# Transfer_V1_Sch.net
KiCad netlist of a schematic drawn in Altium Designer
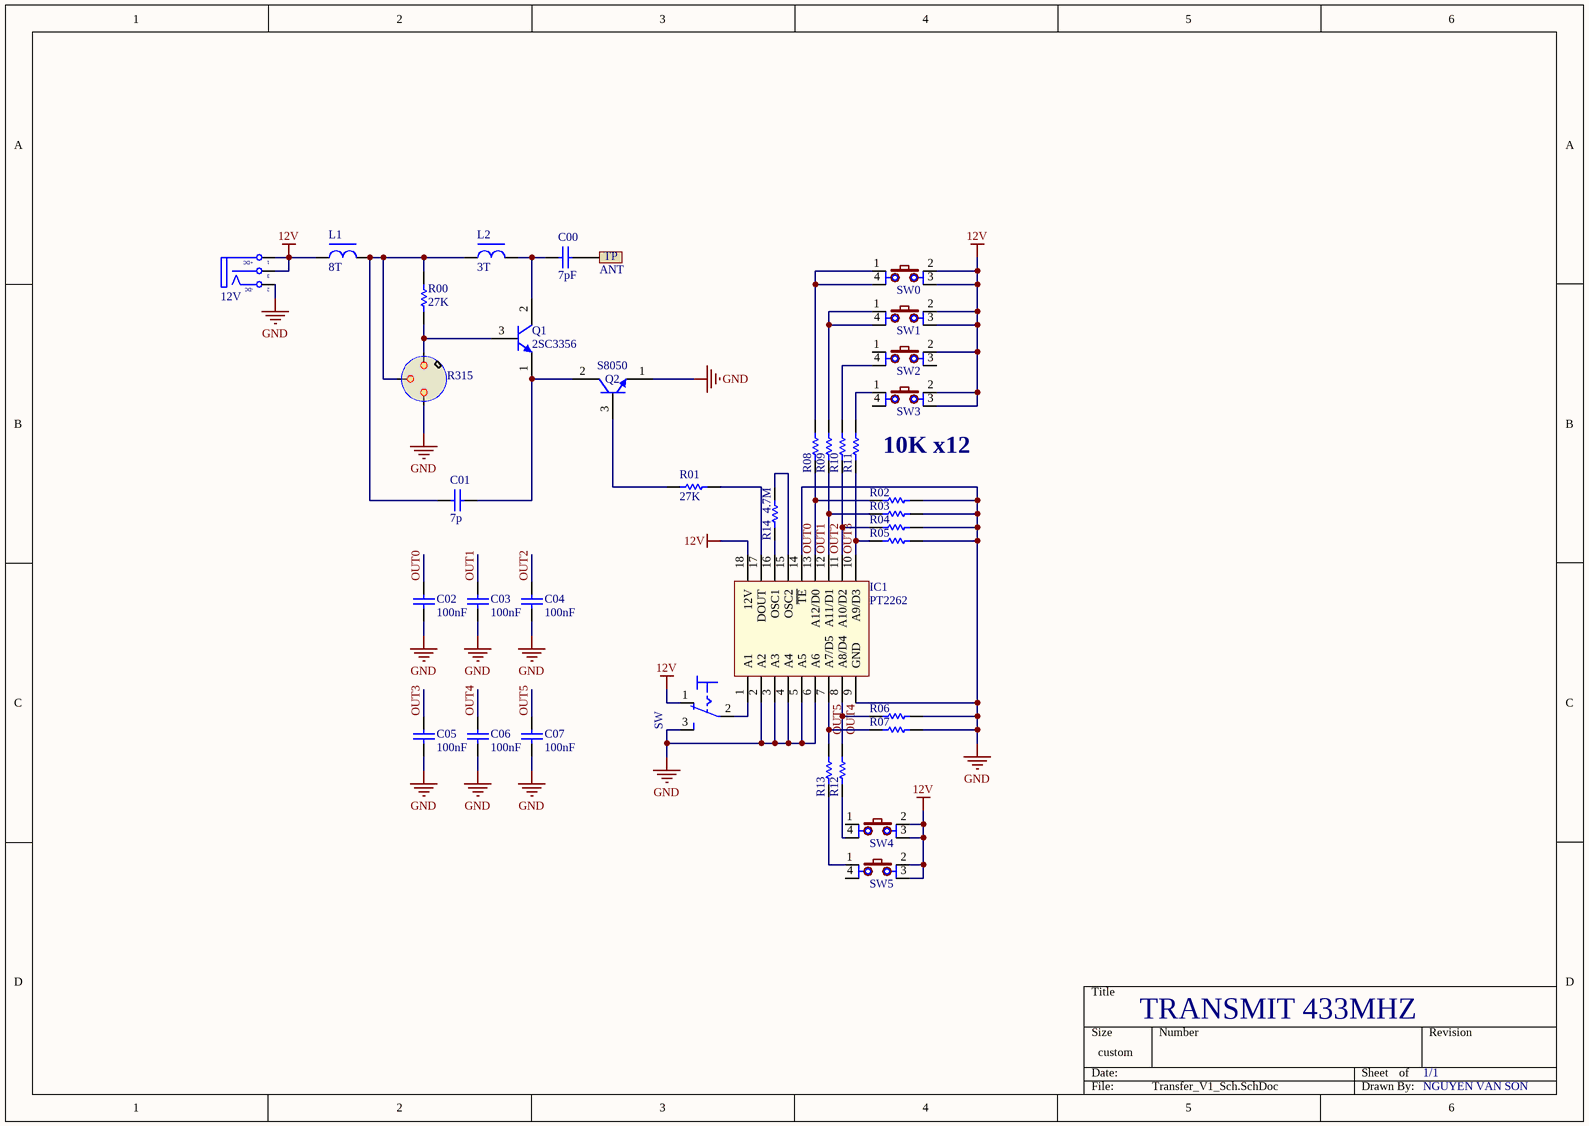
[diagram p0: Transfer_V1_Sch.SchDoc]

(export (version "E")
  (design (tool "Eeschema 10.0.6"))
  (components
    (comp (ref "12V")
      (value "JACK DC 5.5")
      (footprint "JACK DC 5.5")
      (libsource (lib "Altium_Lib_by_KhueNguyenCreator") (part "JACK DC 5.5"))
    )
    (comp (ref "ANT")
      (value "Test Point")
      (footprint "TP")
      (libsource (lib "PIF_Library") (part "Test Point"))
    )
    (comp (ref "C00")
      (value "7pF")
      (footprint "CAP-SM-0603")
      (description "Capacitor")
      (fields (field (name "Comment") "Cap Non-Pol SMD"))
      (libsource (lib "PIF_Library") (part "Cap Non-Pol SMD"))
    )
    (comp (ref "C01")
      (value "7p")
      (footprint "CAP-SM-0603")
      (description "Capacitor")
      (fields (field (name "Comment") "Cap Non-Pol SMD"))
      (libsource (lib "PIF_Library") (part "Cap Non-Pol SMD"))
    )
    (comp (ref "C02")
      (value "100nF")
      (footprint "CAP-SM-0603")
      (description "Capacitor")
      (fields (field (name "Comment") "Cap Non-Pol SMD"))
      (libsource (lib "PIF_Library") (part "Cap Non-Pol SMD"))
    )
    (comp (ref "C03")
      (value "100nF")
      (footprint "CAP-SM-0603")
      (description "Capacitor")
      (fields (field (name "Comment") "Cap Non-Pol SMD"))
      (libsource (lib "PIF_Library") (part "Cap Non-Pol SMD"))
    )
    (comp (ref "C04")
      (value "100nF")
      (footprint "CAP-SM-0603")
      (description "Capacitor")
      (fields (field (name "Comment") "Cap Non-Pol SMD"))
      (libsource (lib "PIF_Library") (part "Cap Non-Pol SMD"))
    )
    (comp (ref "C05")
      (value "100nF")
      (footprint "CAP-SM-0603")
      (description "Capacitor")
      (fields (field (name "Comment") "Cap Non-Pol SMD"))
      (libsource (lib "PIF_Library") (part "Cap Non-Pol SMD"))
    )
    (comp (ref "C06")
      (value "100nF")
      (footprint "CAP-SM-0603")
      (description "Capacitor")
      (fields (field (name "Comment") "Cap Non-Pol SMD"))
      (libsource (lib "PIF_Library") (part "Cap Non-Pol SMD"))
    )
    (comp (ref "C07")
      (value "100nF")
      (footprint "CAP-SM-0603")
      (description "Capacitor")
      (fields (field (name "Comment") "Cap Non-Pol SMD"))
      (libsource (lib "PIF_Library") (part "Cap Non-Pol SMD"))
    )
    (comp (ref "IC1")
      (value "PT2262")
      (footprint "DIP18")
      (description "Remote Control Encoder")
      (libsource (lib "TechMT.VN_Lib_Project v2") (part "PT2262"))
    )
    (comp (ref "L1")
      (value "8T")
      (footprint "L-DIP-M-5.3")
      (description "Inductor")
      (libsource (lib "TechMT.VN_Lib_Project v2") (part "L-DIP-1"))
    )
    (comp (ref "L2")
      (value "3T")
      (footprint "L-DIP-M-5.3")
      (description "Inductor")
      (libsource (lib "TechMT.VN_Lib_Project v2") (part "L-DIP-1"))
    )
    (comp (ref "Q1")
      (value "2SC3356")
      (footprint "SOT23B")
      (description "NPN Bipolar Transistor")
      (libsource (lib "PIF_Library") (part "C1815"))
    )
    (comp (ref "Q2")
      (value "S8050")
      (footprint "SOT23B")
      (description "NPN Bipolar Transistor")
      (libsource (lib "PIF_Library") (part "C1815"))
    )
    (comp (ref "R00")
      (value "27K")
      (footprint "RES-SM-0603")
      (description "Resistor")
      (libsource (lib "PIF_Library") (part "RESISTOR SMD"))
    )
    (comp (ref "R01")
      (value "27K")
      (footprint "RES-SM-0603")
      (description "Resistor")
      (libsource (lib "PIF_Library") (part "RESISTOR SMD"))
    )
    (comp (ref "R02")
      (value "RESISTOR SMD")
      (footprint "RES-SM-0603")
      (description "Resistor")
      (libsource (lib "PIF_Library") (part "RESISTOR SMD"))
    )
    (comp (ref "R03")
      (value "RESISTOR SMD")
      (footprint "RES-SM-0603")
      (description "Resistor")
      (libsource (lib "PIF_Library") (part "RESISTOR SMD"))
    )
    (comp (ref "R04")
      (value "RESISTOR SMD")
      (footprint "RES-SM-0603")
      (description "Resistor")
      (libsource (lib "PIF_Library") (part "RESISTOR SMD"))
    )
    (comp (ref "R05")
      (value "RESISTOR SMD")
      (footprint "RES-SM-0603")
      (description "Resistor")
      (libsource (lib "PIF_Library") (part "RESISTOR SMD"))
    )
    (comp (ref "R06")
      (value "RESISTOR SMD")
      (footprint "RES-SM-0603")
      (description "Resistor")
      (libsource (lib "PIF_Library") (part "RESISTOR SMD"))
    )
    (comp (ref "R07")
      (value "RESISTOR SMD")
      (footprint "RES-SM-0603")
      (description "Resistor")
      (libsource (lib "PIF_Library") (part "RESISTOR SMD"))
    )
    (comp (ref "R08")
      (value "RESISTOR SMD")
      (footprint "RES-SM-0603")
      (description "Resistor")
      (libsource (lib "PIF_Library") (part "RESISTOR SMD"))
    )
    (comp (ref "R09")
      (value "RESISTOR SMD")
      (footprint "RES-SM-0603")
      (description "Resistor")
      (libsource (lib "PIF_Library") (part "RESISTOR SMD"))
    )
    (comp (ref "R10")
      (value "RESISTOR SMD")
      (footprint "RES-SM-0603")
      (description "Resistor")
      (libsource (lib "PIF_Library") (part "RESISTOR SMD"))
    )
    (comp (ref "R11")
      (value "RESISTOR SMD")
      (footprint "RES-SM-0603")
      (description "Resistor")
      (libsource (lib "PIF_Library") (part "RESISTOR SMD"))
    )
    (comp (ref "R12")
      (value "RESISTOR SMD")
      (footprint "RES-SM-0603")
      (description "Resistor")
      (libsource (lib "PIF_Library") (part "RESISTOR SMD"))
    )
    (comp (ref "R13")
      (value "RESISTOR SMD")
      (footprint "RES-SM-0603")
      (description "Resistor")
      (libsource (lib "PIF_Library") (part "RESISTOR SMD"))
    )
    (comp (ref "R14")
      (value "4.7M")
      (footprint "RES-SM-0805")
      (description "Resistor")
      (fields (field (name "Comment") "RESISTOR SMD"))
      (libsource (lib "PIF_Library") (part "RESISTOR SMD"))
    )
    (comp (ref "R315")
      (value "BXR513A")
      (footprint "BXR315A")
      (description "Xtal For RF")
      (libsource (lib "TechMT.VN_Lib_Project v2") (part "BXR315A"))
    )
    (comp (ref "SW")
      (value "MTS-102")
      (footprint "MTS-102")
      (description "Rectangular Cable Assemblies .100 Mini Mate Single Row Discrete Wire Cable Assembly, Terminal")
      (fields (field (name "MF") "Motorola") (field (name "MP") "MTS102"))
      (libsource (lib "MTS-102") (part "MTS-102"))
    )
    (comp (ref "SW0")
      (value "SW")
      (footprint "SW2-DIP")
      (description "Switch button 4 pin")
      (libsource (lib "TechMT.VN_Lib_Project v2") (part "SW4"))
    )
    (comp (ref "SW1")
      (value "SW")
      (footprint "SW2-DIP")
      (description "Switch button 4 pin")
      (libsource (lib "TechMT.VN_Lib_Project v2") (part "SW4"))
    )
    (comp (ref "SW2")
      (value "SW")
      (footprint "SW2-DIP")
      (description "Switch button 4 pin")
      (libsource (lib "TechMT.VN_Lib_Project v2") (part "SW4"))
    )
    (comp (ref "SW3")
      (value "SW")
      (footprint "SW2-DIP")
      (description "Switch button 4 pin")
      (libsource (lib "TechMT.VN_Lib_Project v2") (part "SW4"))
    )
    (comp (ref "SW4")
      (value "SW")
      (footprint "SW2-DIP")
      (description "Switch button 4 pin")
      (libsource (lib "TechMT.VN_Lib_Project v2") (part "SW4"))
    )
    (comp (ref "SW5")
      (value "SW")
      (footprint "SW2-DIP")
      (description "Switch button 4 pin")
      (libsource (lib "TechMT.VN_Lib_Project v2") (part "SW4"))
    )
  )
  (nets
    (net (code "1") (name "/OUT0") (class "Default")
      (node (ref "C02") (pin "2") (pinfunction "2_2") (pintype "passive"))
      (node (ref "IC1") (pin "13") (pinfunction "A12/D0_13") (pintype "passive"))
      (node (ref "R02") (pin "2") (pinfunction "2_2") (pintype "passive"))
      (node (ref "R08") (pin "1") (pinfunction "1_1") (pintype "passive"))
    )
    (net (code "2") (name "/OUT1") (class "Default")
      (node (ref "C03") (pin "2") (pinfunction "2_2") (pintype "passive"))
      (node (ref "IC1") (pin "12") (pinfunction "A11/D1_12") (pintype "passive"))
      (node (ref "R03") (pin "2") (pinfunction "2_2") (pintype "passive"))
      (node (ref "R09") (pin "1") (pinfunction "1_1") (pintype "passive"))
    )
    (net (code "3") (name "/OUT2") (class "Default")
      (node (ref "C04") (pin "2") (pinfunction "2_2") (pintype "passive"))
      (node (ref "IC1") (pin "11") (pinfunction "A10/D2_11") (pintype "passive"))
      (node (ref "R04") (pin "2") (pinfunction "2_2") (pintype "passive"))
      (node (ref "R10") (pin "1") (pinfunction "1_1") (pintype "passive"))
    )
    (net (code "4") (name "/OUT3") (class "Default")
      (node (ref "C05") (pin "2") (pinfunction "2_2") (pintype "passive"))
      (node (ref "IC1") (pin "10") (pinfunction "A9/D3_10") (pintype "passive"))
      (node (ref "R05") (pin "2") (pinfunction "2_2") (pintype "passive"))
      (node (ref "R11") (pin "1") (pinfunction "1_1") (pintype "passive"))
    )
    (net (code "5") (name "/OUT4") (class "Default")
      (node (ref "C06") (pin "2") (pinfunction "2_2") (pintype "passive"))
      (node (ref "IC1") (pin "8") (pinfunction "A8/D4_8") (pintype "passive"))
      (node (ref "R06") (pin "2") (pinfunction "2_2") (pintype "passive"))
      (node (ref "R12") (pin "1") (pinfunction "1_1") (pintype "passive"))
    )
    (net (code "6") (name "/OUT5") (class "Default")
      (node (ref "C07") (pin "2") (pinfunction "2_2") (pintype "passive"))
      (node (ref "IC1") (pin "7") (pinfunction "A7/D5_7") (pintype "passive"))
      (node (ref "R07") (pin "2") (pinfunction "2_2") (pintype "passive"))
      (node (ref "R13") (pin "1") (pinfunction "1_1") (pintype "passive"))
    )
    (net (code "7") (name "12V") (class "Default")
      (node (ref "12V") (pin "1") (pinfunction "T_1") (pintype "passive"))
      (node (ref "12V") (pin "3") (pinfunction "S_3") (pintype "power_in"))
      (node (ref "IC1") (pin "18") (pinfunction "12V_18") (pintype "passive"))
      (node (ref "L1") (pin "1") (pinfunction "1_1") (pintype "passive"))
      (node (ref "SW") (pin "1") (pinfunction "O_1") (pintype "passive"))
      (node (ref "SW0") (pin "2") (pinfunction "2_2") (pintype "passive"))
      (node (ref "SW0") (pin "3") (pinfunction "3_3") (pintype "passive"))
      (node (ref "SW1") (pin "2") (pinfunction "2_2") (pintype "passive"))
      (node (ref "SW1") (pin "3") (pinfunction "3_3") (pintype "passive"))
      (node (ref "SW2") (pin "2") (pinfunction "2_2") (pintype "passive"))
      (node (ref "SW3") (pin "2") (pinfunction "2_2") (pintype "passive"))
      (node (ref "SW3") (pin "3") (pinfunction "3_3") (pintype "passive"))
      (node (ref "SW4") (pin "2") (pinfunction "2_2") (pintype "passive"))
      (node (ref "SW4") (pin "3") (pinfunction "3_3") (pintype "passive"))
      (node (ref "SW5") (pin "2") (pinfunction "2_2") (pintype "passive"))
      (node (ref "SW5") (pin "3") (pinfunction "3_3") (pintype "passive"))
    )
    (net (code "8") (name "GND") (class "Default")
      (node (ref "12V") (pin "2") (pinfunction "TN_2") (pintype "passive"))
      (node (ref "C02") (pin "1") (pinfunction "1_1") (pintype "passive"))
      (node (ref "C03") (pin "1") (pinfunction "1_1") (pintype "passive"))
      (node (ref "C04") (pin "1") (pinfunction "1_1") (pintype "passive"))
      (node (ref "C05") (pin "1") (pinfunction "1_1") (pintype "passive"))
      (node (ref "C06") (pin "1") (pinfunction "1_1") (pintype "passive"))
      (node (ref "C07") (pin "1") (pinfunction "1_1") (pintype "passive"))
      (node (ref "IC1") (pin "14") (pinfunction "~{TE}_14") (pintype "passive"))
      (node (ref "IC1") (pin "2") (pinfunction "A2_2") (pintype "passive"))
      (node (ref "IC1") (pin "3") (pinfunction "A3_3") (pintype "passive"))
      (node (ref "IC1") (pin "4") (pinfunction "A4_4") (pintype "passive"))
      (node (ref "IC1") (pin "5") (pinfunction "A5_5") (pintype "passive"))
      (node (ref "IC1") (pin "6") (pinfunction "A6_6") (pintype "passive"))
      (node (ref "IC1") (pin "9") (pinfunction "GND_9") (pintype "passive"))
      (node (ref "Q2") (pin "1") (pinfunction "E_1") (pintype "passive"))
      (node (ref "R02") (pin "1") (pinfunction "1_1") (pintype "passive"))
      (node (ref "R03") (pin "1") (pinfunction "1_1") (pintype "passive"))
      (node (ref "R04") (pin "1") (pinfunction "1_1") (pintype "passive"))
      (node (ref "R05") (pin "1") (pinfunction "1_1") (pintype "passive"))
      (node (ref "R06") (pin "1") (pinfunction "1_1") (pintype "passive"))
      (node (ref "R07") (pin "1") (pinfunction "1_1") (pintype "passive"))
      (node (ref "R315") (pin "3") (pinfunction "3_3") (pintype "passive"))
      (node (ref "SW") (pin "3") (pinfunction "S_3") (pintype "passive"))
    )
    (net (code "9") (name "Net-(ANT-0)") (class "Default")
      (node (ref "ANT") (pin "TP1") (pinfunction "0_TP1") (pintype "passive"))
      (node (ref "C00") (pin "1") (pinfunction "1_1") (pintype "passive"))
    )
    (net (code "10") (name "Net-(C01-Pad1)") (class "Default")
      (node (ref "C01") (pin "1") (pinfunction "1_1") (pintype "passive"))
      (node (ref "L1") (pin "2") (pinfunction "2_2") (pintype "passive"))
      (node (ref "L2") (pin "1") (pinfunction "1_1") (pintype "passive"))
      (node (ref "R00") (pin "1") (pinfunction "1_1") (pintype "passive"))
      (node (ref "R315") (pin "2") (pinfunction "2_2") (pintype "passive"))
    )
    (net (code "11") (name "Net-(IC1-A1)") (class "Default")
      (node (ref "IC1") (pin "1") (pinfunction "A1_1") (pintype "passive"))
      (node (ref "SW") (pin "2") (pinfunction "P_2") (pintype "passive"))
    )
    (net (code "12") (name "Net-(IC1-DOUT)") (class "Default")
      (node (ref "IC1") (pin "17") (pinfunction "DOUT_17") (pintype "passive"))
      (node (ref "R01") (pin "2") (pinfunction "2_2") (pintype "passive"))
    )
    (net (code "13") (name "Net-(IC1-OSC1)") (class "Default")
      (node (ref "IC1") (pin "16") (pinfunction "OSC1_16") (pintype "passive"))
      (node (ref "R14") (pin "2") (pinfunction "2_2") (pintype "passive"))
    )
    (net (code "14") (name "Net-(IC1-OSC2)") (class "Default")
      (node (ref "IC1") (pin "15") (pinfunction "OSC2_15") (pintype "passive"))
      (node (ref "R14") (pin "1") (pinfunction "1_1") (pintype "passive"))
    )
    (net (code "15") (name "Net-(Q1-B)") (class "Default")
      (node (ref "Q1") (pin "3") (pinfunction "B_3") (pintype "passive"))
      (node (ref "R00") (pin "2") (pinfunction "2_2") (pintype "passive"))
      (node (ref "R315") (pin "1") (pinfunction "1_1") (pintype "passive"))
    )
    (net (code "16") (name "Net-(Q1-C)") (class "Default")
      (node (ref "C00") (pin "2") (pinfunction "2_2") (pintype "passive"))
      (node (ref "L2") (pin "2") (pinfunction "2_2") (pintype "passive"))
      (node (ref "Q1") (pin "2") (pinfunction "C_2") (pintype "passive"))
    )
    (net (code "17") (name "Net-(Q1-E)") (class "Default")
      (node (ref "C01") (pin "2") (pinfunction "2_2") (pintype "passive"))
      (node (ref "Q1") (pin "1") (pinfunction "E_1") (pintype "passive"))
      (node (ref "Q2") (pin "2") (pinfunction "C_2") (pintype "passive"))
    )
    (net (code "18") (name "Net-(Q2-B)") (class "Default")
      (node (ref "Q2") (pin "3") (pinfunction "B_3") (pintype "passive"))
      (node (ref "R01") (pin "1") (pinfunction "1_1") (pintype "passive"))
    )
    (net (code "19") (name "Net-(R08-Pad2)") (class "Default")
      (node (ref "R08") (pin "2") (pinfunction "2_2") (pintype "passive"))
      (node (ref "SW0") (pin "1") (pintype "passive"))
      (node (ref "SW0") (pin "4") (pinfunction "4_4") (pintype "passive"))
    )
    (net (code "20") (name "Net-(R09-Pad2)") (class "Default")
      (node (ref "R09") (pin "2") (pinfunction "2_2") (pintype "passive"))
      (node (ref "SW1") (pin "1") (pintype "passive"))
      (node (ref "SW1") (pin "4") (pinfunction "4_4") (pintype "passive"))
    )
    (net (code "21") (name "Net-(R10-Pad2)") (class "Default")
      (node (ref "R10") (pin "2") (pinfunction "2_2") (pintype "passive"))
      (node (ref "SW2") (pin "4") (pinfunction "4_4") (pintype "passive"))
    )
    (net (code "22") (name "Net-(R11-Pad2)") (class "Default")
      (node (ref "R11") (pin "2") (pinfunction "2_2") (pintype "passive"))
      (node (ref "SW3") (pin "1") (pintype "passive"))
    )
    (net (code "23") (name "Net-(R12-Pad2)") (class "Default")
      (node (ref "R12") (pin "2") (pinfunction "2_2") (pintype "passive"))
      (node (ref "SW4") (pin "4") (pinfunction "4_4") (pintype "passive"))
    )
    (net (code "24") (name "Net-(R13-Pad2)") (class "Default")
      (node (ref "R13") (pin "2") (pinfunction "2_2") (pintype "passive"))
      (node (ref "SW5") (pin "1") (pintype "passive"))
    )
    (net (code "25") (name "unconnected-(SW2-Pad1)") (class "Default")
      (node (ref "SW2") (pin "1") (pintype "passive"))
    )
    (net (code "26") (name "unconnected-(SW2-Pad3)") (class "Default")
      (node (ref "SW2") (pin "3") (pinfunction "3_3") (pintype "passive"))
    )
    (net (code "27") (name "unconnected-(SW3-Pad4)") (class "Default")
      (node (ref "SW3") (pin "4") (pinfunction "4_4") (pintype "passive"))
    )
    (net (code "28") (name "unconnected-(SW4-Pad1)") (class "Default")
      (node (ref "SW4") (pin "1") (pintype "passive"))
    )
    (net (code "29") (name "unconnected-(SW5-Pad4)") (class "Default")
      (node (ref "SW5") (pin "4") (pinfunction "4_4") (pintype "passive"))
    )
  )
)
